# schematic.net
KiCad netlist of a schematic drawn in Altium Designer
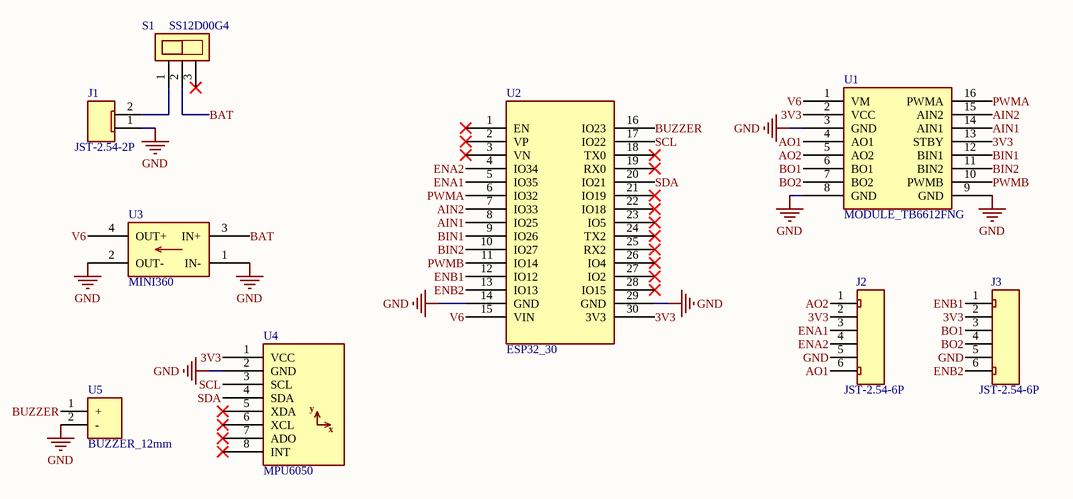
[diagram p0: schematic.SchDoc]

(export (version "E")
  (design (tool "Eeschema 10.0.6"))
  (components
    (comp (ref "J1")
      (value "JST-2.54-2P")
      (footprint "JST-2.54-2P")
      (description "Female Connector JST 2 Vias, 2.54mm.")
      (libsource (lib "Connectors") (part "JST-2.54-2P"))
    )
    (comp (ref "J2")
      (value "JST-2.54-6P")
      (footprint "JST-2.54-6P")
      (description "Female Connector JST 6 Vias, 2.54mm.")
      (libsource (lib "Connectors") (part "JST-2.54-6P"))
    )
    (comp (ref "J3")
      (value "JST-2.54-6P")
      (footprint "JST-2.54-6P")
      (description "Female Connector JST 6 Vias, 2.54mm.")
      (libsource (lib "Connectors") (part "JST-2.54-6P"))
    )
    (comp (ref "S1")
      (value "SS12D00G4")
      (footprint "SS12D00G4")
      (libsource (lib "Buttons & Switches") (part "SS12D00G4"))
    )
    (comp (ref "U1")
      (value "MODULE_TB6612FNG")
      (footprint "MODULE_TB6612FNG")
      (description "Module Dual Motor Driver 2.5-13.5V 3.2A Peak 21x18mm")
      (libsource (lib "Motor Drivers") (part "MODULE_TB6612FNG"))
    )
    (comp (ref "U2")
      (value "ESP32_30")
      (footprint "ESP32_30")
      (description "Microcontoller Board 30 Pins Wifi 2.4GHz BLE 4.2 ESP32-WROOM-32D")
      (libsource (lib "Espressif Microcontrollers") (part "ESP32_30"))
    )
    (comp (ref "U3")
      (value "MINI360")
      (footprint "MINI360")
      (description "MODULE BUCK STEP DOWN 3A 18x12mm")
      (libsource (lib "Voltage Regulators") (part "MINI360"))
    )
    (comp (ref "U4")
      (value "MPU6050")
      (footprint "MPU6050")
      (description "IMU ACCEL/GYRO 3-AXIS I2C")
      (libsource (lib "Sensors") (part "MPU6050"))
    )
    (comp (ref "U5")
      (value "BUZZER_12mm")
      (footprint "BUZZER_12mm")
      (description "BUZZER MAGNETIC 12MM")
      (libsource (lib "Random") (part "BUZZER_12mm"))
    )
  )
  (nets
    (net (code "1") (name "/3V3") (class "Default")
      (node (ref "J2") (pin "2") (pintype "passive"))
      (node (ref "J3") (pin "2") (pintype "passive"))
      (node (ref "U1") (pin "13") (pinfunction "STBY_13") (pintype "passive"))
      (node (ref "U1") (pin "2") (pinfunction "VCC_2") (pintype "passive"))
      (node (ref "U2") (pin "30") (pinfunction "3V3_30") (pintype "passive"))
      (node (ref "U4") (pin "1") (pinfunction "VCC_1") (pintype "passive"))
    )
    (net (code "2") (name "/AIN1") (class "Default")
      (node (ref "U1") (pin "14") (pinfunction "AIN1_14") (pintype "passive"))
      (node (ref "U2") (pin "8") (pinfunction "IO25_8") (pintype "passive"))
    )
    (net (code "3") (name "/AIN2") (class "Default")
      (node (ref "U1") (pin "15") (pinfunction "AIN2_15") (pintype "passive"))
      (node (ref "U2") (pin "7") (pinfunction "IO33_7") (pintype "passive"))
    )
    (net (code "4") (name "/AO1") (class "Default")
      (node (ref "J2") (pin "6") (pintype "passive"))
      (node (ref "U1") (pin "4") (pinfunction "AO1_4") (pintype "passive"))
    )
    (net (code "5") (name "/AO2") (class "Default")
      (node (ref "J2") (pin "1") (pintype "passive"))
      (node (ref "U1") (pin "5") (pinfunction "AO2_5") (pintype "passive"))
    )
    (net (code "6") (name "/BAT") (class "Default")
      (node (ref "S1") (pin "2") (pintype "passive"))
      (node (ref "U3") (pin "3") (pinfunction "IN+_3") (pintype "passive"))
    )
    (net (code "7") (name "/BIN1") (class "Default")
      (node (ref "U1") (pin "12") (pinfunction "BIN1_12") (pintype "passive"))
      (node (ref "U2") (pin "9") (pinfunction "IO26_9") (pintype "passive"))
    )
    (net (code "8") (name "/BIN2") (class "Default")
      (node (ref "U1") (pin "11") (pinfunction "BIN2_11") (pintype "passive"))
      (node (ref "U2") (pin "10") (pinfunction "IO27_10") (pintype "passive"))
    )
    (net (code "9") (name "/BO1") (class "Default")
      (node (ref "J3") (pin "3") (pintype "passive"))
      (node (ref "U1") (pin "6") (pinfunction "BO1_6") (pintype "passive"))
    )
    (net (code "10") (name "/BO2") (class "Default")
      (node (ref "J3") (pin "4") (pintype "passive"))
      (node (ref "U1") (pin "7") (pinfunction "BO2_7") (pintype "passive"))
    )
    (net (code "11") (name "/BUZZER") (class "Default")
      (node (ref "U2") (pin "16") (pinfunction "IO23_16") (pintype "passive"))
      (node (ref "U5") (pin "1") (pinfunction "+_1") (pintype "passive"))
    )
    (net (code "12") (name "/ENA1") (class "Default")
      (node (ref "J2") (pin "3") (pintype "passive"))
      (node (ref "U2") (pin "5") (pinfunction "IO35_5") (pintype "passive"))
    )
    (net (code "13") (name "/ENA2") (class "Default")
      (node (ref "J2") (pin "4") (pintype "passive"))
      (node (ref "U2") (pin "4") (pinfunction "IO34_4") (pintype "passive"))
    )
    (net (code "14") (name "/ENB1") (class "Default")
      (node (ref "J3") (pin "1") (pintype "passive"))
      (node (ref "U2") (pin "12") (pinfunction "IO12_12") (pintype "passive"))
    )
    (net (code "15") (name "/ENB2") (class "Default")
      (node (ref "J3") (pin "6") (pintype "passive"))
      (node (ref "U2") (pin "13") (pinfunction "IO13_13") (pintype "passive"))
    )
    (net (code "16") (name "/PWMA") (class "Default")
      (node (ref "U1") (pin "16") (pinfunction "PWMA_16") (pintype "passive"))
      (node (ref "U2") (pin "6") (pinfunction "IO32_6") (pintype "passive"))
    )
    (net (code "17") (name "/PWMB") (class "Default")
      (node (ref "U1") (pin "10") (pinfunction "PWMB_10") (pintype "passive"))
      (node (ref "U2") (pin "11") (pinfunction "IO14_11") (pintype "passive"))
    )
    (net (code "18") (name "/SCL") (class "Default")
      (node (ref "U2") (pin "17") (pinfunction "IO22_17") (pintype "passive"))
      (node (ref "U4") (pin "3") (pinfunction "SCL_3") (pintype "passive"))
    )
    (net (code "19") (name "/SDA") (class "Default")
      (node (ref "U2") (pin "20") (pinfunction "IO21_20") (pintype "passive"))
      (node (ref "U4") (pin "4") (pinfunction "SDA_4") (pintype "passive"))
    )
    (net (code "20") (name "/V6") (class "Default")
      (node (ref "U1") (pin "1") (pinfunction "VM_1") (pintype "passive"))
      (node (ref "U2") (pin "15") (pinfunction "VIN_15") (pintype "passive"))
      (node (ref "U3") (pin "4") (pinfunction "OUT+_4") (pintype "passive"))
    )
    (net (code "21") (name "GND") (class "Default")
      (node (ref "J1") (pin "1") (pintype "passive"))
      (node (ref "J2") (pin "5") (pintype "passive"))
      (node (ref "J3") (pin "5") (pintype "passive"))
      (node (ref "U1") (pin "3") (pinfunction "GND_3") (pintype "passive"))
      (node (ref "U1") (pin "8") (pinfunction "GND_8") (pintype "passive"))
      (node (ref "U1") (pin "9") (pinfunction "GND_9") (pintype "passive"))
      (node (ref "U2") (pin "14") (pinfunction "GND_14") (pintype "passive"))
      (node (ref "U2") (pin "29") (pinfunction "GND_29") (pintype "passive"))
      (node (ref "U3") (pin "1") (pinfunction "IN-_1") (pintype "passive"))
      (node (ref "U3") (pin "2") (pinfunction "OUT-_2") (pintype "passive"))
      (node (ref "U4") (pin "2") (pinfunction "GND_2") (pintype "passive"))
      (node (ref "U5") (pin "2") (pinfunction "-_2") (pintype "passive"))
    )
    (net (code "22") (name "Net-(J1-Pad2)") (class "Default")
      (node (ref "J1") (pin "2") (pintype "passive"))
      (node (ref "S1") (pin "1") (pintype "passive"))
    )
    (net (code "23") (name "unconnected-(S1-Pad3)") (class "Default")
      (node (ref "S1") (pin "3") (pintype "passive+no_connect"))
    )
    (net (code "24") (name "unconnected-(U2-EN-Pad1)") (class "Default")
      (node (ref "U2") (pin "1") (pinfunction "EN_1") (pintype "passive+no_connect"))
    )
    (net (code "25") (name "unconnected-(U2-IO2-Pad27)") (class "Default")
      (node (ref "U2") (pin "27") (pinfunction "IO2_27") (pintype "passive+no_connect"))
    )
    (net (code "26") (name "unconnected-(U2-IO4-Pad26)") (class "Default")
      (node (ref "U2") (pin "26") (pinfunction "IO4_26") (pintype "passive+no_connect"))
    )
    (net (code "27") (name "unconnected-(U2-IO5-Pad23)") (class "Default")
      (node (ref "U2") (pin "23") (pinfunction "IO5_23") (pintype "passive+no_connect"))
    )
    (net (code "28") (name "unconnected-(U2-IO15-Pad28)") (class "Default")
      (node (ref "U2") (pin "28") (pinfunction "IO15_28") (pintype "passive+no_connect"))
    )
    (net (code "29") (name "unconnected-(U2-IO18-Pad22)") (class "Default")
      (node (ref "U2") (pin "22") (pinfunction "IO18_22") (pintype "passive+no_connect"))
    )
    (net (code "30") (name "unconnected-(U2-IO19-Pad21)") (class "Default")
      (node (ref "U2") (pin "21") (pinfunction "IO19_21") (pintype "passive+no_connect"))
    )
    (net (code "31") (name "unconnected-(U2-RX0-Pad19)") (class "Default")
      (node (ref "U2") (pin "19") (pinfunction "RX0_19") (pintype "passive+no_connect"))
    )
    (net (code "32") (name "unconnected-(U2-RX2-Pad25)") (class "Default")
      (node (ref "U2") (pin "25") (pinfunction "RX2_25") (pintype "passive+no_connect"))
    )
    (net (code "33") (name "unconnected-(U2-TX0-Pad18)") (class "Default")
      (node (ref "U2") (pin "18") (pinfunction "TX0_18") (pintype "passive+no_connect"))
    )
    (net (code "34") (name "unconnected-(U2-TX2-Pad24)") (class "Default")
      (node (ref "U2") (pin "24") (pinfunction "TX2_24") (pintype "passive+no_connect"))
    )
    (net (code "35") (name "unconnected-(U2-VN-Pad3)") (class "Default")
      (node (ref "U2") (pin "3") (pinfunction "VN_3") (pintype "passive+no_connect"))
    )
    (net (code "36") (name "unconnected-(U2-VP-Pad2)") (class "Default")
      (node (ref "U2") (pin "2") (pinfunction "VP_2") (pintype "passive+no_connect"))
    )
    (net (code "37") (name "unconnected-(U4-ADO-Pad7)") (class "Default")
      (node (ref "U4") (pin "7") (pinfunction "ADO_7") (pintype "passive+no_connect"))
    )
    (net (code "38") (name "unconnected-(U4-INT-Pad8)") (class "Default")
      (node (ref "U4") (pin "8") (pinfunction "INT_8") (pintype "passive+no_connect"))
    )
    (net (code "39") (name "unconnected-(U4-XCL-Pad6)") (class "Default")
      (node (ref "U4") (pin "6") (pinfunction "XCL_6") (pintype "passive+no_connect"))
    )
    (net (code "40") (name "unconnected-(U4-XDA-Pad5)") (class "Default")
      (node (ref "U4") (pin "5") (pinfunction "XDA_5") (pintype "passive+no_connect"))
    )
  )
)
